# SparkFun_Qwiic_Micro_Barometer_LPS28DFW.net
KiCad netlist of a schematic drawn in EAGLE
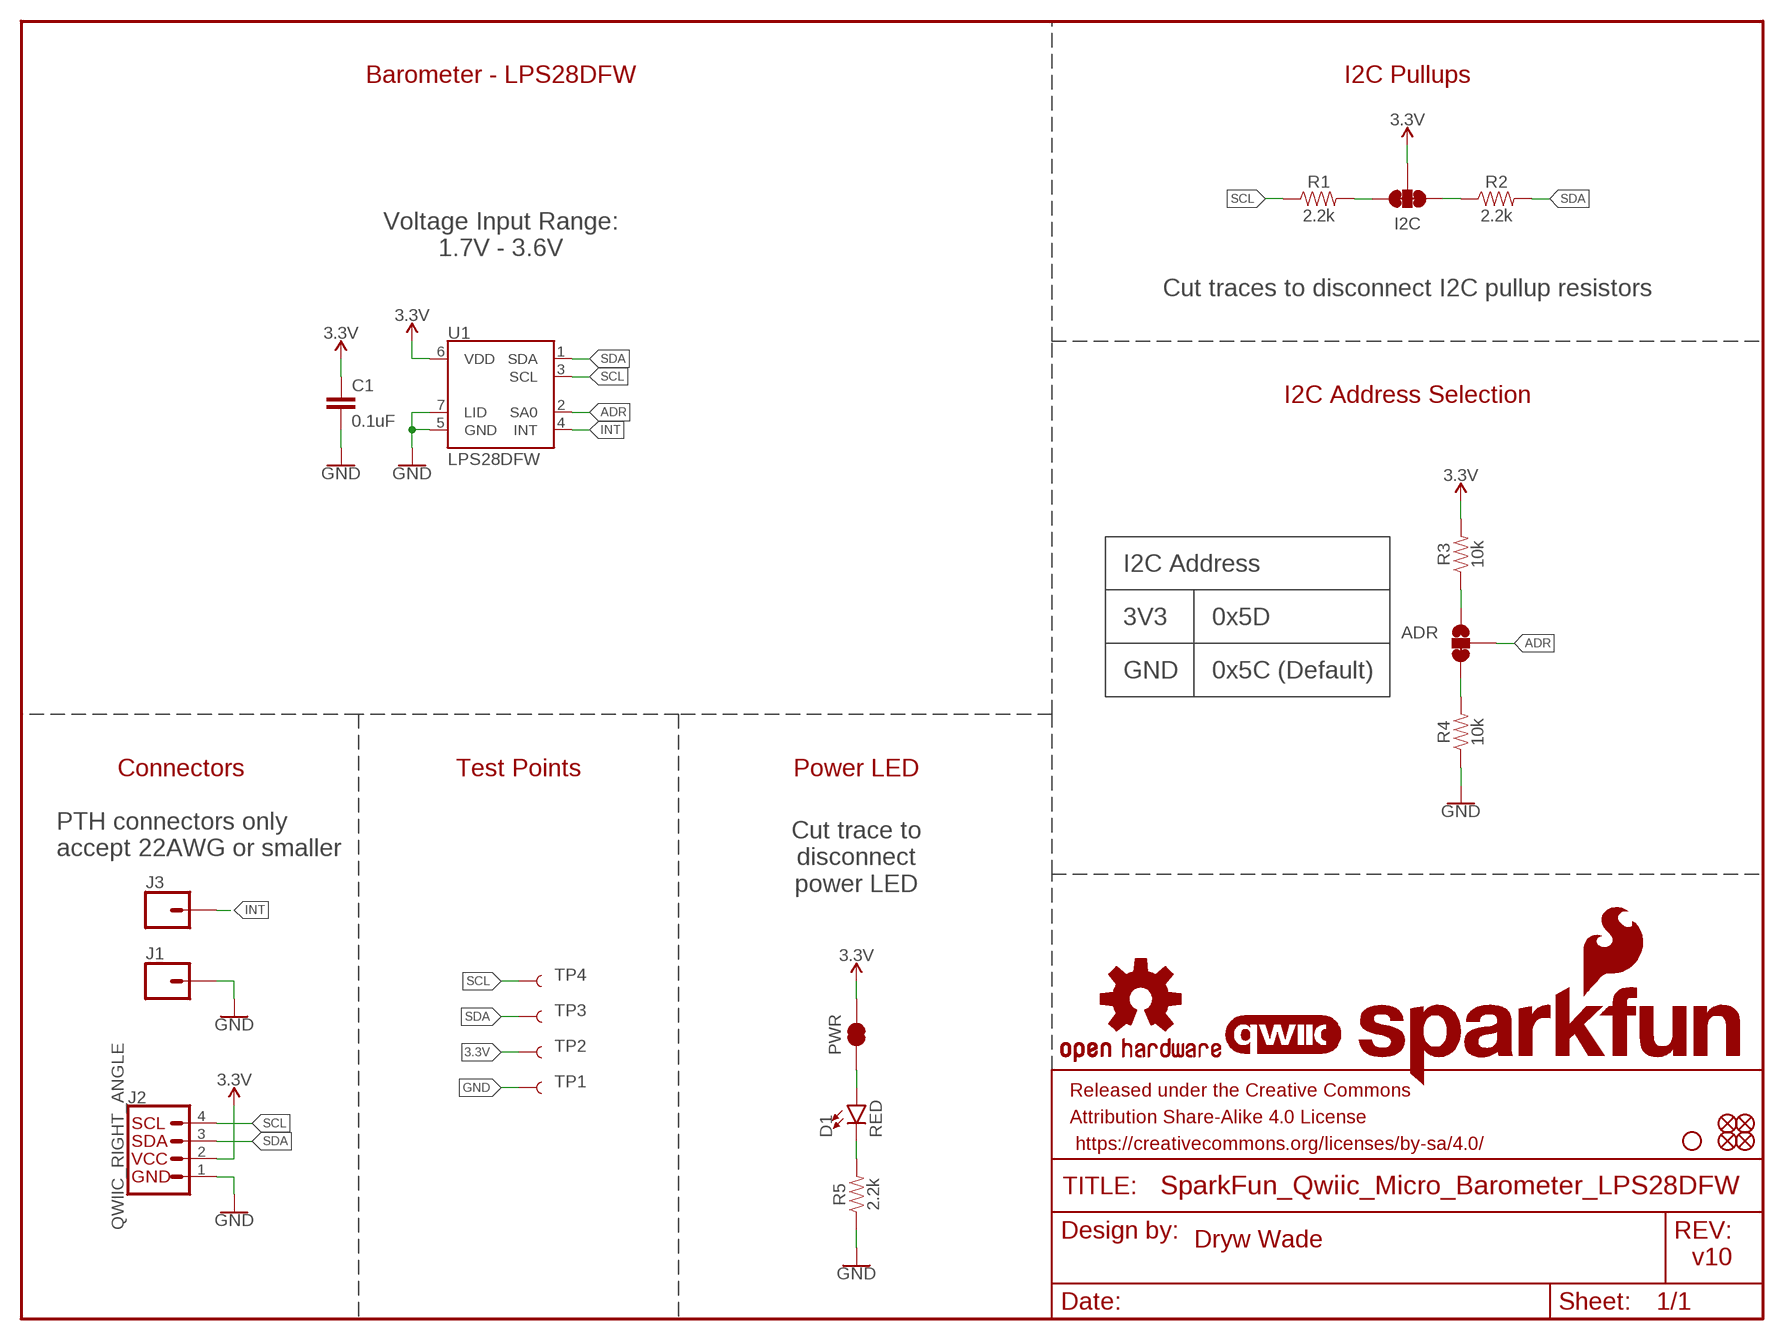
[diagram p0: schematic, sheet 1]

(export (version "E")
  (design (tool "Eeschema 10.0.6"))
  (components
    (comp (ref "ADR")
      (value "JUMPER-SMT_3_1-NC_TRACE_SILK")
      (footprint "eagle-import:SMT-JUMPER_3_1-NC_TRACE_SILK")
      (libsource (lib "eagle-import") (part "JUMPER-SMT_3_1-NC_TRACE_SILK"))
    )
    (comp (ref "C1")
      (value "0.1uF")
      (footprint "eagle-import:0402-TIGHT")
      (libsource (lib "eagle-import") (part "0.1UF-0402T-16V-10%"))
    )
    (comp (ref "D1")
      (value "RED")
      (footprint "eagle-import:LED-0402")
      (libsource (lib "eagle-import") (part "LED-RED_0402"))
    )
    (comp (ref "FD1")
      (value "FIDUCIALUFIDUCIAL")
      (footprint "eagle-import:FIDUCIAL-MICRO")
      (libsource (lib "eagle-import") (part "FIDUCIALUFIDUCIAL"))
    )
    (comp (ref "FD2")
      (value "FIDUCIALUFIDUCIAL")
      (footprint "eagle-import:FIDUCIAL-MICRO")
      (libsource (lib "eagle-import") (part "FIDUCIALUFIDUCIAL"))
    )
    (comp (ref "FD3")
      (value "FIDUCIALUFIDUCIAL")
      (footprint "eagle-import:FIDUCIAL-MICRO")
      (libsource (lib "eagle-import") (part "FIDUCIALUFIDUCIAL"))
    )
    (comp (ref "FD4")
      (value "FIDUCIALUFIDUCIAL")
      (footprint "eagle-import:FIDUCIAL-MICRO")
      (libsource (lib "eagle-import") (part "FIDUCIALUFIDUCIAL"))
    )
    (comp (ref "FRAME1")
      (value "FRAME-LETTER")
      (footprint "eagle-import:CREATIVE_COMMONS")
      (libsource (lib "eagle-import") (part "FRAME-LETTER"))
    )
    (comp (ref "H1")
      (value "STAND-OFF")
      (footprint "eagle-import:STAND-OFF")
      (libsource (lib "eagle-import") (part "STAND-OFF"))
    )
    (comp (ref "I2C")
      (value "JUMPER-SMT_3_2-NC_TRACE_SILK")
      (footprint "eagle-import:SMT-JUMPER_3_2-NC_TRACE_SILK")
      (libsource (lib "eagle-import") (part "JUMPER-SMT_3_2-NC_TRACE_SILK"))
    )
    (comp (ref "J1")
      (value "CONN_01_1MM")
      (footprint "eagle-import:1X01_1MM_NO_SILK")
      (libsource (lib "eagle-import") (part "CONN_01_1MM"))
    )
    (comp (ref "J2")
      (value "QWIIC_RIGHT_ANGLE")
      (footprint "eagle-import:JST04_1MM_RA")
      (libsource (lib "eagle-import") (part "QWIIC_CONNECTORJS-1MM"))
    )
    (comp (ref "J3")
      (value "CONN_01_1MM")
      (footprint "eagle-import:1X01_1MM_NO_SILK")
      (libsource (lib "eagle-import") (part "CONN_01_1MM"))
    )
    (comp (ref "LOGO1")
      (value "OSHW-LOGOS")
      (footprint "eagle-import:OSHW-LOGO-S")
      (libsource (lib "eagle-import") (part "OSHW-LOGOS"))
    )
    (comp (ref "LOGO2")
      (value "QWIIC_LOGO_3MM")
      (footprint "eagle-import:QWIIC_3MM")
      (libsource (lib "eagle-import") (part "QWIIC_LOGO_3MM"))
    )
    (comp (ref "LOGO3")
      (value "SFE_LOGO_NAME_FLAMEBLANK")
      (footprint "eagle-import:BLANK")
      (libsource (lib "eagle-import") (part "SFE_LOGO_NAME_FLAMEBLANK"))
    )
    (comp (ref "PWR")
      (value "JUMPER-SMT_2_NC_TRACE_SILK")
      (footprint "eagle-import:SMT-JUMPER_2_NC_TRACE_SILK")
      (libsource (lib "eagle-import") (part "JUMPER-SMT_2_NC_TRACE_SILK"))
    )
    (comp (ref "R1")
      (value "2.2k")
      (footprint "eagle-import:0402-TIGHT")
      (libsource (lib "eagle-import") (part "2.2KOHM-0402T-1/16W-1%"))
    )
    (comp (ref "R2")
      (value "2.2k")
      (footprint "eagle-import:0402-TIGHT")
      (libsource (lib "eagle-import") (part "2.2KOHM-0402T-1/16W-1%"))
    )
    (comp (ref "R3")
      (value "10k")
      (footprint "eagle-import:0402-TIGHT")
      (libsource (lib "eagle-import") (part "10KOHM-0402T-1/16W-1%"))
    )
    (comp (ref "R4")
      (value "10k")
      (footprint "eagle-import:0402-TIGHT")
      (libsource (lib "eagle-import") (part "10KOHM-0402T-1/16W-1%"))
    )
    (comp (ref "R5")
      (value "2.2k")
      (footprint "eagle-import:0402-TIGHT")
      (libsource (lib "eagle-import") (part "2.2KOHM-0402T-1/16W-1%"))
    )
    (comp (ref "TP1")
      (value "TEST-POINT3")
      (footprint "eagle-import:PAD.03X.03")
      (libsource (lib "eagle-import") (part "TEST-POINT3"))
    )
    (comp (ref "TP2")
      (value "TEST-POINT3")
      (footprint "eagle-import:PAD.03X.03")
      (libsource (lib "eagle-import") (part "TEST-POINT3"))
    )
    (comp (ref "TP3")
      (value "TEST-POINT3")
      (footprint "eagle-import:PAD.03X.03")
      (libsource (lib "eagle-import") (part "TEST-POINT3"))
    )
    (comp (ref "TP4")
      (value "TEST-POINT3")
      (footprint "eagle-import:PAD.03X.03")
      (libsource (lib "eagle-import") (part "TEST-POINT3"))
    )
    (comp (ref "U1")
      (value "LPS28DFW")
      (footprint "eagle-import:CCLGA-7L")
      (libsource (lib "eagle-import") (part "LPS28DFW"))
    )
  )
  (nets
    (net (code "1") (name "3.3V") (class "Default")
      (node (ref "C1") (pin "1") (pinfunction "1_1") (pintype "passive"))
      (node (ref "I2C") (pin "2") (pinfunction "2_2") (pintype "passive"))
      (node (ref "J2") (pin "2") (pinfunction "2_2") (pintype "power_in"))
      (node (ref "PWR") (pin "2") (pinfunction "2_2") (pintype "passive"))
      (node (ref "R3") (pin "2") (pinfunction "2_2") (pintype "passive"))
      (node (ref "TP2") (pin "1") (pinfunction "1_1") (pintype "bidirectional"))
      (node (ref "U1") (pin "6") (pinfunction "VDD_6") (pintype "power_in"))
    )
    (net (code "2") (name "ADR") (class "Default")
      (node (ref "ADR") (pin "2") (pinfunction "2_2") (pintype "passive"))
      (node (ref "U1") (pin "2") (pinfunction "SA0_2") (pintype "input"))
    )
    (net (code "3") (name "GND") (class "Default")
      (node (ref "C1") (pin "2") (pinfunction "2_2") (pintype "passive"))
      (node (ref "J1") (pin "1") (pinfunction "1_1") (pintype "passive"))
      (node (ref "J2") (pin "1") (pinfunction "1_1") (pintype "power_in"))
      (node (ref "R4") (pin "1") (pinfunction "1_1") (pintype "passive"))
      (node (ref "R5") (pin "1") (pinfunction "1_1") (pintype "passive"))
      (node (ref "TP1") (pin "1") (pinfunction "1_1") (pintype "bidirectional"))
      (node (ref "U1") (pin "5") (pinfunction "GND_5") (pintype "power_in"))
      (node (ref "U1") (pin "7") (pinfunction "LID_7") (pintype "passive"))
    )
    (net (code "4") (name "INT") (class "Default")
      (node (ref "J3") (pin "1") (pinfunction "1_1") (pintype "passive"))
      (node (ref "U1") (pin "4") (pinfunction "INT_4") (pintype "output"))
    )
    (net (code "5") (name "Net-(ADR-Pad1)") (class "Default")
      (node (ref "ADR") (pin "1") (pinfunction "1_1") (pintype "passive"))
      (node (ref "R3") (pin "1") (pinfunction "1_1") (pintype "passive"))
    )
    (net (code "6") (name "Net-(ADR-Pad3)") (class "Default")
      (node (ref "ADR") (pin "3") (pinfunction "3_3") (pintype "passive"))
      (node (ref "R4") (pin "2") (pinfunction "2_2") (pintype "passive"))
    )
    (net (code "7") (name "Net-(D1-PadA)") (class "Default")
      (node (ref "D1") (pin "A") (pinfunction "A_A") (pintype "passive"))
      (node (ref "PWR") (pin "1") (pinfunction "1_1") (pintype "passive"))
    )
    (net (code "8") (name "Net-(D1-PadC)") (class "Default")
      (node (ref "D1") (pin "C") (pinfunction "C_C") (pintype "passive"))
      (node (ref "R5") (pin "2") (pinfunction "2_2") (pintype "passive"))
    )
    (net (code "9") (name "Net-(I2C-Pad1)") (class "Default")
      (node (ref "I2C") (pin "1") (pinfunction "1_1") (pintype "passive"))
      (node (ref "R2") (pin "1") (pinfunction "1_1") (pintype "passive"))
    )
    (net (code "10") (name "Net-(I2C-Pad3)") (class "Default")
      (node (ref "I2C") (pin "3") (pinfunction "3_3") (pintype "passive"))
      (node (ref "R1") (pin "2") (pinfunction "2_2") (pintype "passive"))
    )
    (net (code "11") (name "SCL") (class "Default")
      (node (ref "J2") (pin "4") (pinfunction "4_4") (pintype "passive"))
      (node (ref "R1") (pin "1") (pinfunction "1_1") (pintype "passive"))
      (node (ref "TP4") (pin "1") (pinfunction "1_1") (pintype "bidirectional"))
      (node (ref "U1") (pin "3") (pinfunction "SCL_3") (pintype "input"))
    )
    (net (code "12") (name "SDA") (class "Default")
      (node (ref "J2") (pin "3") (pinfunction "3_3") (pintype "passive"))
      (node (ref "R2") (pin "2") (pinfunction "2_2") (pintype "passive"))
      (node (ref "TP3") (pin "1") (pinfunction "1_1") (pintype "bidirectional"))
      (node (ref "U1") (pin "1") (pinfunction "SDA_1") (pintype "bidirectional"))
    )
  )
)
